# 2312_Interface.net
KiCad netlist of a schematic drawn in Altium Designer
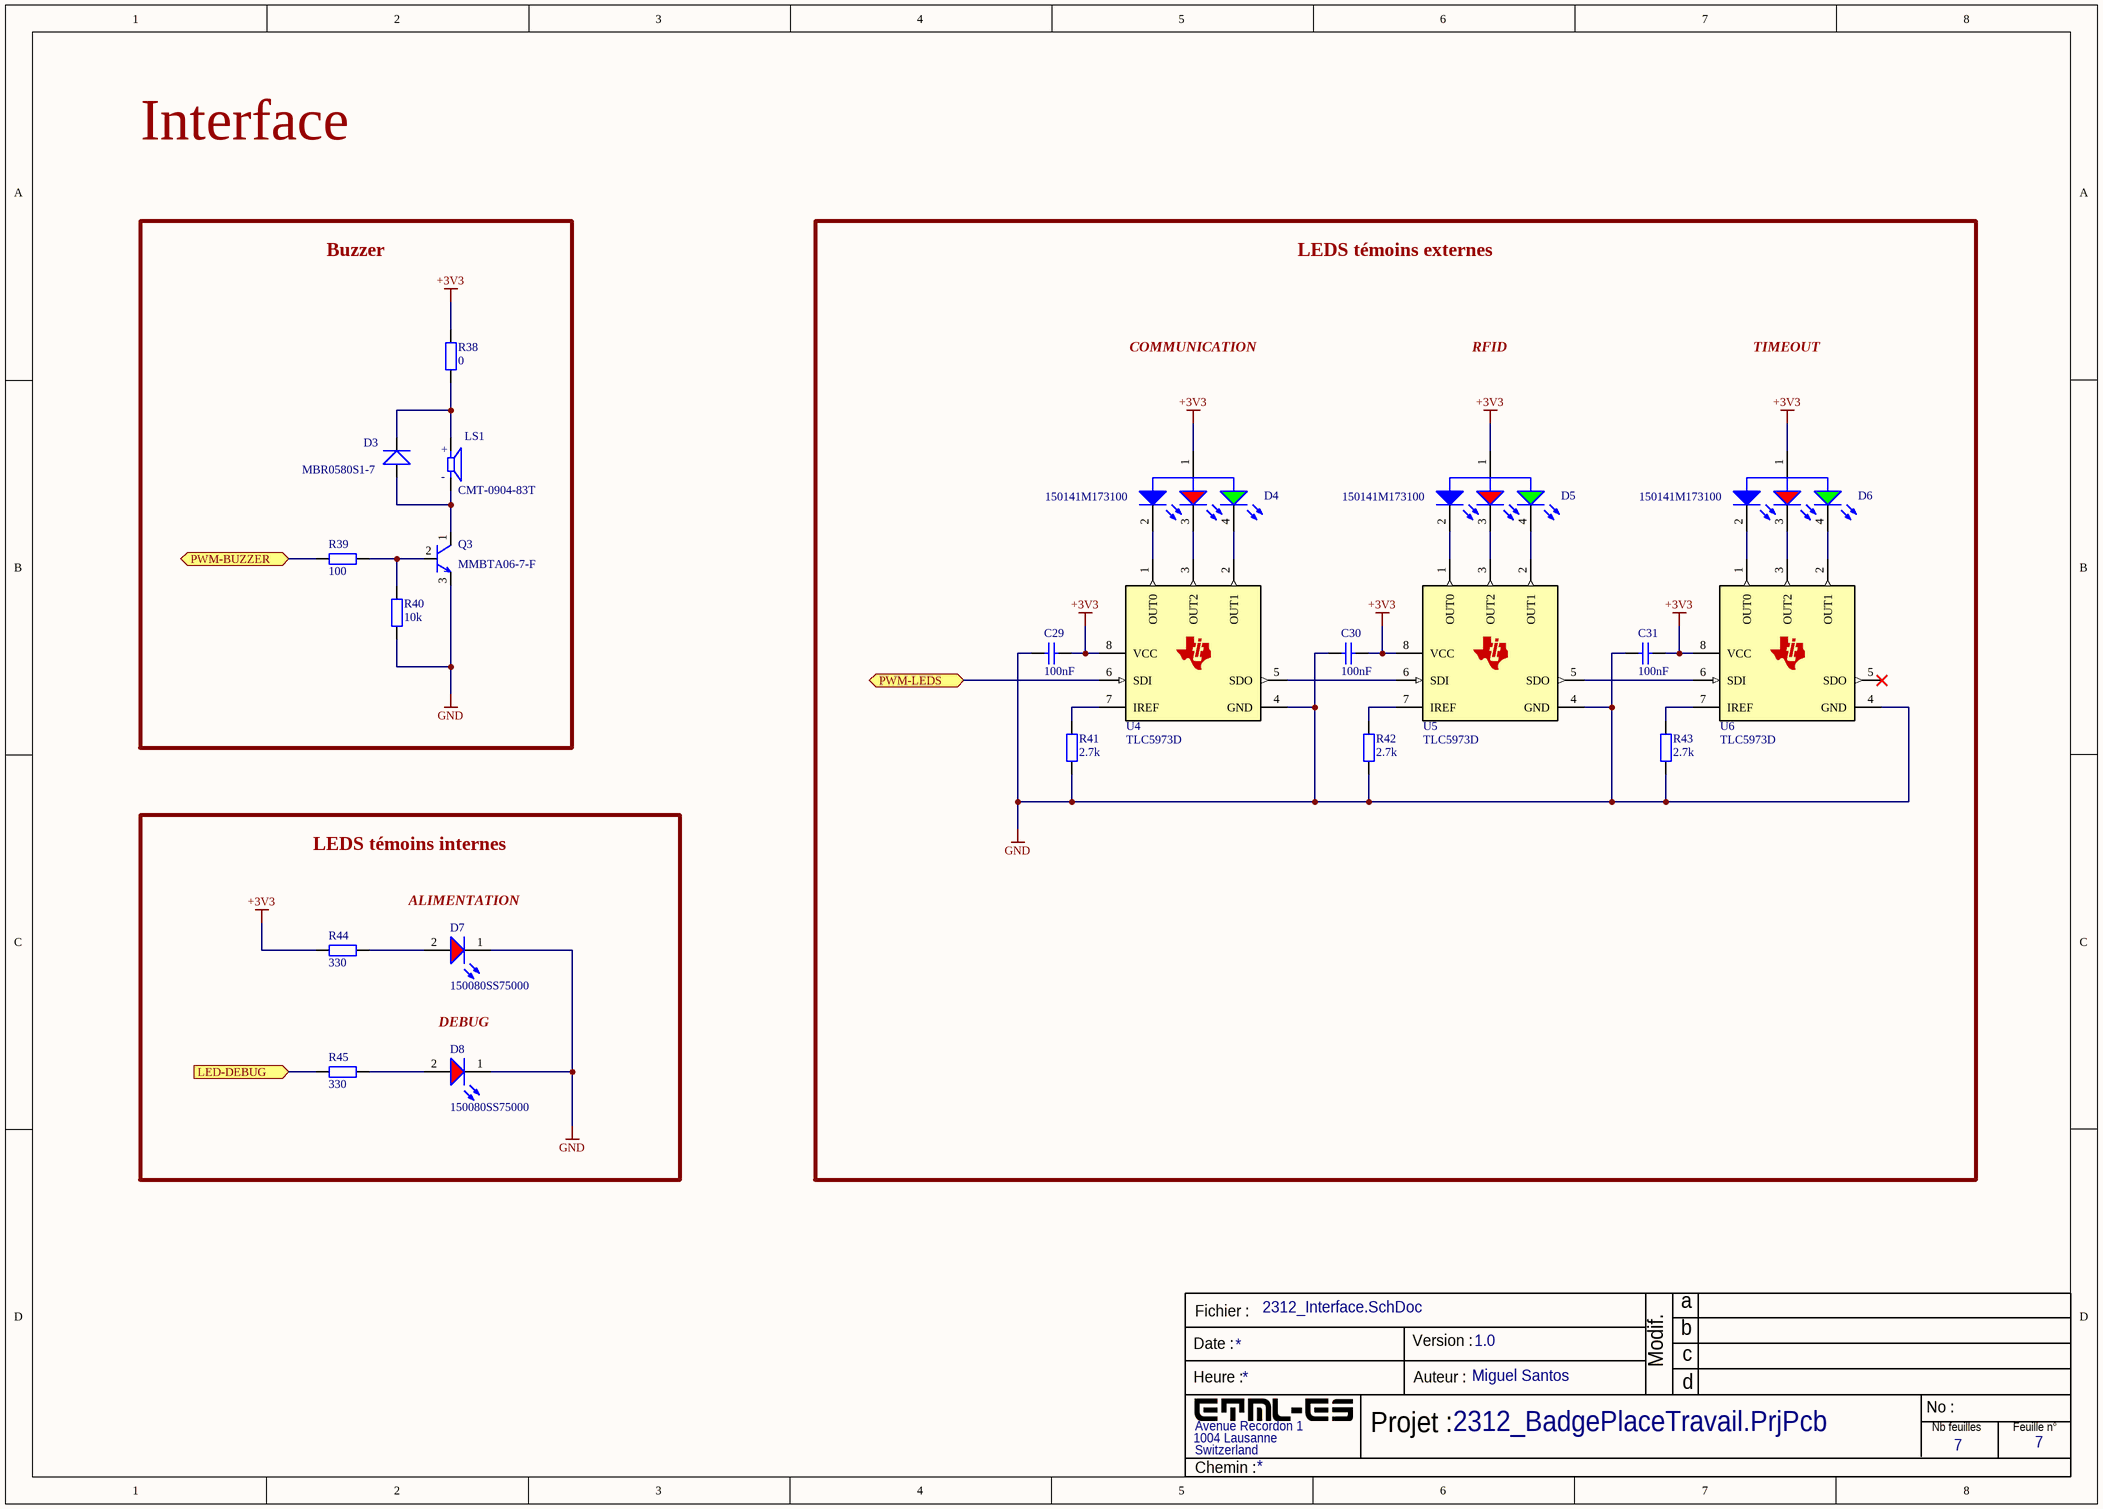
[diagram p0: 2312_Interface.SchDoc]

(export (version "E")
  (design (tool "Eeschema 10.0.6"))
  (components
    (comp (ref "C29")
      (value "885012207016")
      (footprint "WCAP-CSGP_0805_L2W1.25H0.8_Reflow")
      (description "WCAP-CSGP Multilayer Ceramic Chip Capacitor, General Purpose, size 0805, X7R, 100nF, 10VDC")
      (fields (field (name "MANUFACTURER") "Wurth Elektronik") (field (name "CAPACITANCE") "100nF"))
      (libsource (lib "WCAP-CSGP") (part "885012207016"))
    )
    (comp (ref "C30")
      (value "885012207016")
      (footprint "WCAP-CSGP_0805_L2W1.25H0.8_Reflow")
      (description "WCAP-CSGP Multilayer Ceramic Chip Capacitor, General Purpose, size 0805, X7R, 100nF, 10VDC")
      (fields (field (name "MANUFACTURER") "Wurth Elektronik") (field (name "CAPACITANCE") "100nF"))
      (libsource (lib "WCAP-CSGP") (part "885012207016"))
    )
    (comp (ref "C31")
      (value "885012207016")
      (footprint "WCAP-CSGP_0805_L2W1.25H0.8_Reflow")
      (description "WCAP-CSGP Multilayer Ceramic Chip Capacitor, General Purpose, size 0805, X7R, 100nF, 10VDC")
      (fields (field (name "MANUFACTURER") "Wurth Elektronik") (field (name "CAPACITANCE") "100nF"))
      (libsource (lib "WCAP-CSGP") (part "885012207016"))
    )
    (comp (ref "D3")
      (value "MBR0580S1-7")
      (footprint "MBR0580S1-7_DIO")
      (description "Diode Shottky, 500mA, 80V")
      (libsource (lib "MBR0580S1-7") (part "MBR0580S1-7"))
    )
    (comp (ref "D4")
      (value "150141M173100")
      (footprint "WL-SFTW_3528_150141M173100")
      (description "WL-SFTW Full-color TOP LED Waterclear, size 3528, Red & Green & Blue, 120°")
      (fields (field (name "MANUFACTURER") "Wurth Elektronik"))
      (libsource (lib "WL-SFTW") (part "150141M173100"))
    )
    (comp (ref "D5")
      (value "150141M173100")
      (footprint "WL-SFTW_3528_150141M173100")
      (description "WL-SFTW Full-color TOP LED Waterclear, size 3528, Red & Green & Blue, 120°")
      (fields (field (name "MANUFACTURER") "Wurth Elektronik"))
      (libsource (lib "WL-SFTW") (part "150141M173100"))
    )
    (comp (ref "D6")
      (value "150141M173100")
      (footprint "WL-SFTW_3528_150141M173100")
      (description "WL-SFTW Full-color TOP LED Waterclear, size 3528, Red & Green & Blue, 120°")
      (fields (field (name "MANUFACTURER") "Wurth Elektronik"))
      (libsource (lib "WL-SFTW") (part "150141M173100"))
    )
    (comp (ref "D7")
      (value "150080SS75000")
      (footprint "WL-SMCW_0805_150080xx75000")
      (description "WL-SMCW Mono-color Chip LED Waterclear, size 0805, Super Red, 1.9V, 140°")
      (fields (field (name "MANUFACTURER") "Wurth Elektronik"))
      (libsource (lib "WL-SMCW") (part "150080SS75000"))
    )
    (comp (ref "D8")
      (value "150080SS75000")
      (footprint "WL-SMCW_0805_150080xx75000")
      (description "WL-SMCW Mono-color Chip LED Waterclear, size 0805, Super Red, 1.9V, 140°")
      (fields (field (name "MANUFACTURER") "Wurth Elektronik"))
      (libsource (lib "WL-SMCW") (part "150080SS75000"))
    )
    (comp (ref "LS1")
      (value "CMT-0904-83T")
      (footprint "XDCR_CMT-0904-83T")
      (description "Buzzer Magnetic, 15Ω")
      (libsource (lib "CMT-0904-83T") (part "CMT-0904-83T"))
    )
    (comp (ref "Q3")
      (value "MMBTA06-7-F")
      (footprint "SOT91P240X120-3N")
      (description "Bipolar (BJT) Transistor NPN 80V 500mA 100MHz 225mW Surface Mount SOT-23-3 (TO-236)")
      (libsource (lib "MMBTA06-7-F") (part "MMBTA06LT3G"))
    )
    (comp (ref "R38")
      (value "RES-0805")
      (footprint "2312-RES-0805")
      (description "SMD Resistor 0805, 0Ω")
      (fields (field (name "RESISTANCE") "0"))
      (libsource (lib "2312-MS-0805") (part "RES-0805"))
    )
    (comp (ref "R39")
      (value "RES-0805")
      (footprint "2312-RES-0805")
      (description "SMD Resistor 0805, 140Ω")
      (fields (field (name "RESISTANCE") "100"))
      (libsource (lib "2312-MS-0805") (part "RES-0805"))
    )
    (comp (ref "R40")
      (value "RES-0805")
      (footprint "2312-RES-0805")
      (description "SMD Resistor 0805, 10kΩ")
      (fields (field (name "RESISTANCE") "10k"))
      (libsource (lib "2312-MS-0805") (part "RES-0805"))
    )
    (comp (ref "R41")
      (value "RES-0805")
      (footprint "2312-RES-0805")
      (description "SMD Resistor 0805, 2.6kΩ")
      (fields (field (name "RESISTANCE") "2.7k"))
      (libsource (lib "2312-MS-0805") (part "RES-0805"))
    )
    (comp (ref "R42")
      (value "RES-0805")
      (footprint "2312-RES-0805")
      (description "SMD Resistor 0805, 2.6kΩ")
      (fields (field (name "RESISTANCE") "2.7k"))
      (libsource (lib "2312-MS-0805") (part "RES-0805"))
    )
    (comp (ref "R43")
      (value "RES-0805")
      (footprint "2312-RES-0805")
      (description "SMD Resistor 0805, 2.6kΩ")
      (fields (field (name "RESISTANCE") "2.7k"))
      (libsource (lib "2312-MS-0805") (part "RES-0805"))
    )
    (comp (ref "R44")
      (value "RES-0805")
      (footprint "2312-RES-0805")
      (description "SMD Resistor 0805, 330Ω")
      (fields (field (name "RESISTANCE") "330"))
      (libsource (lib "2312-MS-0805") (part "RES-0805"))
    )
    (comp (ref "R45")
      (value "RES-0805")
      (footprint "2312-RES-0805")
      (description "SMD Resistor 0805, 330Ω")
      (fields (field (name "RESISTANCE") "330"))
      (libsource (lib "2312-MS-0805") (part "RES-0805"))
    )
    (comp (ref "U4")
      (value "TLC5973D")
      (footprint "D0008A_M")
      (description "No Description Available")
      (libsource (lib "TLC5973D") (part "TLC5973D"))
    )
    (comp (ref "U5")
      (value "TLC5973D")
      (footprint "D0008A_M")
      (description "No Description Available")
      (libsource (lib "TLC5973D") (part "TLC5973D"))
    )
    (comp (ref "U6")
      (value "TLC5973D")
      (footprint "D0008A_M")
      (description "No Description Available")
      (libsource (lib "TLC5973D") (part "TLC5973D"))
    )
  )
  (nets
    (net (code "1") (name "+3V3") (class "Default")
      (node (ref "C29") (pin "2") (pinfunction "2_2") (pintype "passive"))
      (node (ref "C30") (pin "2") (pinfunction "2_2") (pintype "passive"))
      (node (ref "C31") (pin "2") (pinfunction "2_2") (pintype "passive"))
      (node (ref "D4") (pin "1") (pinfunction "A_1") (pintype "passive"))
      (node (ref "D5") (pin "1") (pinfunction "A_1") (pintype "passive"))
      (node (ref "D6") (pin "1") (pinfunction "A_1") (pintype "passive"))
      (node (ref "R38") (pin "2") (pinfunction "2_2") (pintype "passive"))
      (node (ref "R44") (pin "1") (pinfunction "1_1") (pintype "passive"))
      (node (ref "U4") (pin "8") (pinfunction "VCC_8") (pintype "power_in"))
      (node (ref "U5") (pin "8") (pinfunction "VCC_8") (pintype "power_in"))
      (node (ref "U6") (pin "8") (pinfunction "VCC_8") (pintype "power_in"))
    )
    (net (code "2") (name "/LED-DEBUG") (class "Default")
      (node (ref "R45") (pin "1") (pinfunction "1_1") (pintype "passive"))
    )
    (net (code "3") (name "/PWM-BUZZER") (class "Default")
      (node (ref "R39") (pin "2") (pinfunction "2_2") (pintype "passive"))
    )
    (net (code "4") (name "/PWM-LEDS") (class "Default")
      (node (ref "U4") (pin "6") (pinfunction "SDI_6") (pintype "input"))
    )
    (net (code "5") (name "GND") (class "Default")
      (node (ref "C29") (pin "1") (pinfunction "1_1") (pintype "passive"))
      (node (ref "C30") (pin "1") (pinfunction "1_1") (pintype "passive"))
      (node (ref "C31") (pin "1") (pinfunction "1_1") (pintype "passive"))
      (node (ref "D7") (pin "1") (pinfunction "K_1") (pintype "passive"))
      (node (ref "D8") (pin "1") (pinfunction "K_1") (pintype "passive"))
      (node (ref "Q3") (pin "3") (pinfunction "EMITTER_3") (pintype "passive"))
      (node (ref "R40") (pin "2") (pinfunction "2_2") (pintype "passive"))
      (node (ref "R41") (pin "1") (pinfunction "1_1") (pintype "passive"))
      (node (ref "R42") (pin "1") (pinfunction "1_1") (pintype "passive"))
      (node (ref "R43") (pin "1") (pinfunction "1_1") (pintype "passive"))
      (node (ref "U4") (pin "4") (pinfunction "GND_4") (pintype "power_in"))
      (node (ref "U5") (pin "4") (pinfunction "GND_4") (pintype "power_in"))
      (node (ref "U6") (pin "4") (pinfunction "GND_4") (pintype "power_in"))
    )
    (net (code "6") (name "Net-(D3-Pad2)") (class "Default")
      (node (ref "D3") (pin "2") (pinfunction "2_2") (pintype "passive"))
      (node (ref "LS1") (pin "P") (pinfunction "P_P") (pintype "passive"))
      (node (ref "R38") (pin "1") (pinfunction "1_1") (pintype "passive"))
    )
    (net (code "7") (name "Net-(D7-A)") (class "Default")
      (node (ref "D7") (pin "2") (pinfunction "A_2") (pintype "passive"))
      (node (ref "R44") (pin "2") (pinfunction "2_2") (pintype "passive"))
    )
    (net (code "8") (name "Net-(D8-A)") (class "Default")
      (node (ref "D8") (pin "2") (pinfunction "A_2") (pintype "passive"))
      (node (ref "R45") (pin "2") (pinfunction "2_2") (pintype "passive"))
    )
    (net (code "9") (name "Net-(Q3-BASE)") (class "Default")
      (node (ref "Q3") (pin "2") (pinfunction "BASE_2") (pintype "passive"))
      (node (ref "R39") (pin "1") (pinfunction "1_1") (pintype "passive"))
      (node (ref "R40") (pin "1") (pinfunction "1_1") (pintype "passive"))
    )
    (net (code "10") (name "Net-(Q3-COLLECTOR)") (class "Default")
      (node (ref "D3") (pin "1") (pinfunction "1_1") (pintype "passive"))
      (node (ref "LS1") (pin "N") (pinfunction "N_N") (pintype "passive"))
      (node (ref "Q3") (pin "1") (pinfunction "COLLECTOR_1") (pintype "passive"))
    )
    (net (code "11") (name "Net-(U4-IREF)") (class "Default")
      (node (ref "R41") (pin "2") (pinfunction "2_2") (pintype "passive"))
      (node (ref "U4") (pin "7") (pinfunction "IREF_7") (pintype "passive"))
    )
    (net (code "12") (name "Net-(U4-OUT0)") (class "Default")
      (node (ref "D4") (pin "2") (pinfunction "K_2") (pintype "passive"))
      (node (ref "U4") (pin "1") (pinfunction "OUT0_1") (pintype "output"))
    )
    (net (code "13") (name "Net-(U4-OUT1)") (class "Default")
      (node (ref "D4") (pin "4") (pinfunction "K_4") (pintype "passive"))
      (node (ref "U4") (pin "2") (pinfunction "OUT1_2") (pintype "output"))
    )
    (net (code "14") (name "Net-(U4-OUT2)") (class "Default")
      (node (ref "D4") (pin "3") (pinfunction "K_3") (pintype "passive"))
      (node (ref "U4") (pin "3") (pinfunction "OUT2_3") (pintype "output"))
    )
    (net (code "15") (name "Net-(U4-SDO)") (class "Default")
      (node (ref "U4") (pin "5") (pinfunction "SDO_5") (pintype "output"))
      (node (ref "U5") (pin "6") (pinfunction "SDI_6") (pintype "input"))
    )
    (net (code "16") (name "Net-(U5-IREF)") (class "Default")
      (node (ref "R42") (pin "2") (pinfunction "2_2") (pintype "passive"))
      (node (ref "U5") (pin "7") (pinfunction "IREF_7") (pintype "passive"))
    )
    (net (code "17") (name "Net-(U5-OUT0)") (class "Default")
      (node (ref "D5") (pin "2") (pinfunction "K_2") (pintype "passive"))
      (node (ref "U5") (pin "1") (pinfunction "OUT0_1") (pintype "output"))
    )
    (net (code "18") (name "Net-(U5-OUT1)") (class "Default")
      (node (ref "D5") (pin "4") (pinfunction "K_4") (pintype "passive"))
      (node (ref "U5") (pin "2") (pinfunction "OUT1_2") (pintype "output"))
    )
    (net (code "19") (name "Net-(U5-OUT2)") (class "Default")
      (node (ref "D5") (pin "3") (pinfunction "K_3") (pintype "passive"))
      (node (ref "U5") (pin "3") (pinfunction "OUT2_3") (pintype "output"))
    )
    (net (code "20") (name "Net-(U5-SDO)") (class "Default")
      (node (ref "U5") (pin "5") (pinfunction "SDO_5") (pintype "output"))
      (node (ref "U6") (pin "6") (pinfunction "SDI_6") (pintype "input"))
    )
    (net (code "21") (name "Net-(U6-IREF)") (class "Default")
      (node (ref "R43") (pin "2") (pinfunction "2_2") (pintype "passive"))
      (node (ref "U6") (pin "7") (pinfunction "IREF_7") (pintype "passive"))
    )
    (net (code "22") (name "Net-(U6-OUT0)") (class "Default")
      (node (ref "D6") (pin "2") (pinfunction "K_2") (pintype "passive"))
      (node (ref "U6") (pin "1") (pinfunction "OUT0_1") (pintype "output"))
    )
    (net (code "23") (name "Net-(U6-OUT1)") (class "Default")
      (node (ref "D6") (pin "4") (pinfunction "K_4") (pintype "passive"))
      (node (ref "U6") (pin "2") (pinfunction "OUT1_2") (pintype "output"))
    )
    (net (code "24") (name "Net-(U6-OUT2)") (class "Default")
      (node (ref "D6") (pin "3") (pinfunction "K_3") (pintype "passive"))
      (node (ref "U6") (pin "3") (pinfunction "OUT2_3") (pintype "output"))
    )
    (net (code "25") (name "unconnected-(U6-SDO-Pad5)") (class "Default")
      (node (ref "U6") (pin "5") (pinfunction "SDO_5") (pintype "output+no_connect"))
    )
  )
)
